# PCB.net
KiCad netlist of a schematic drawn in EAGLE
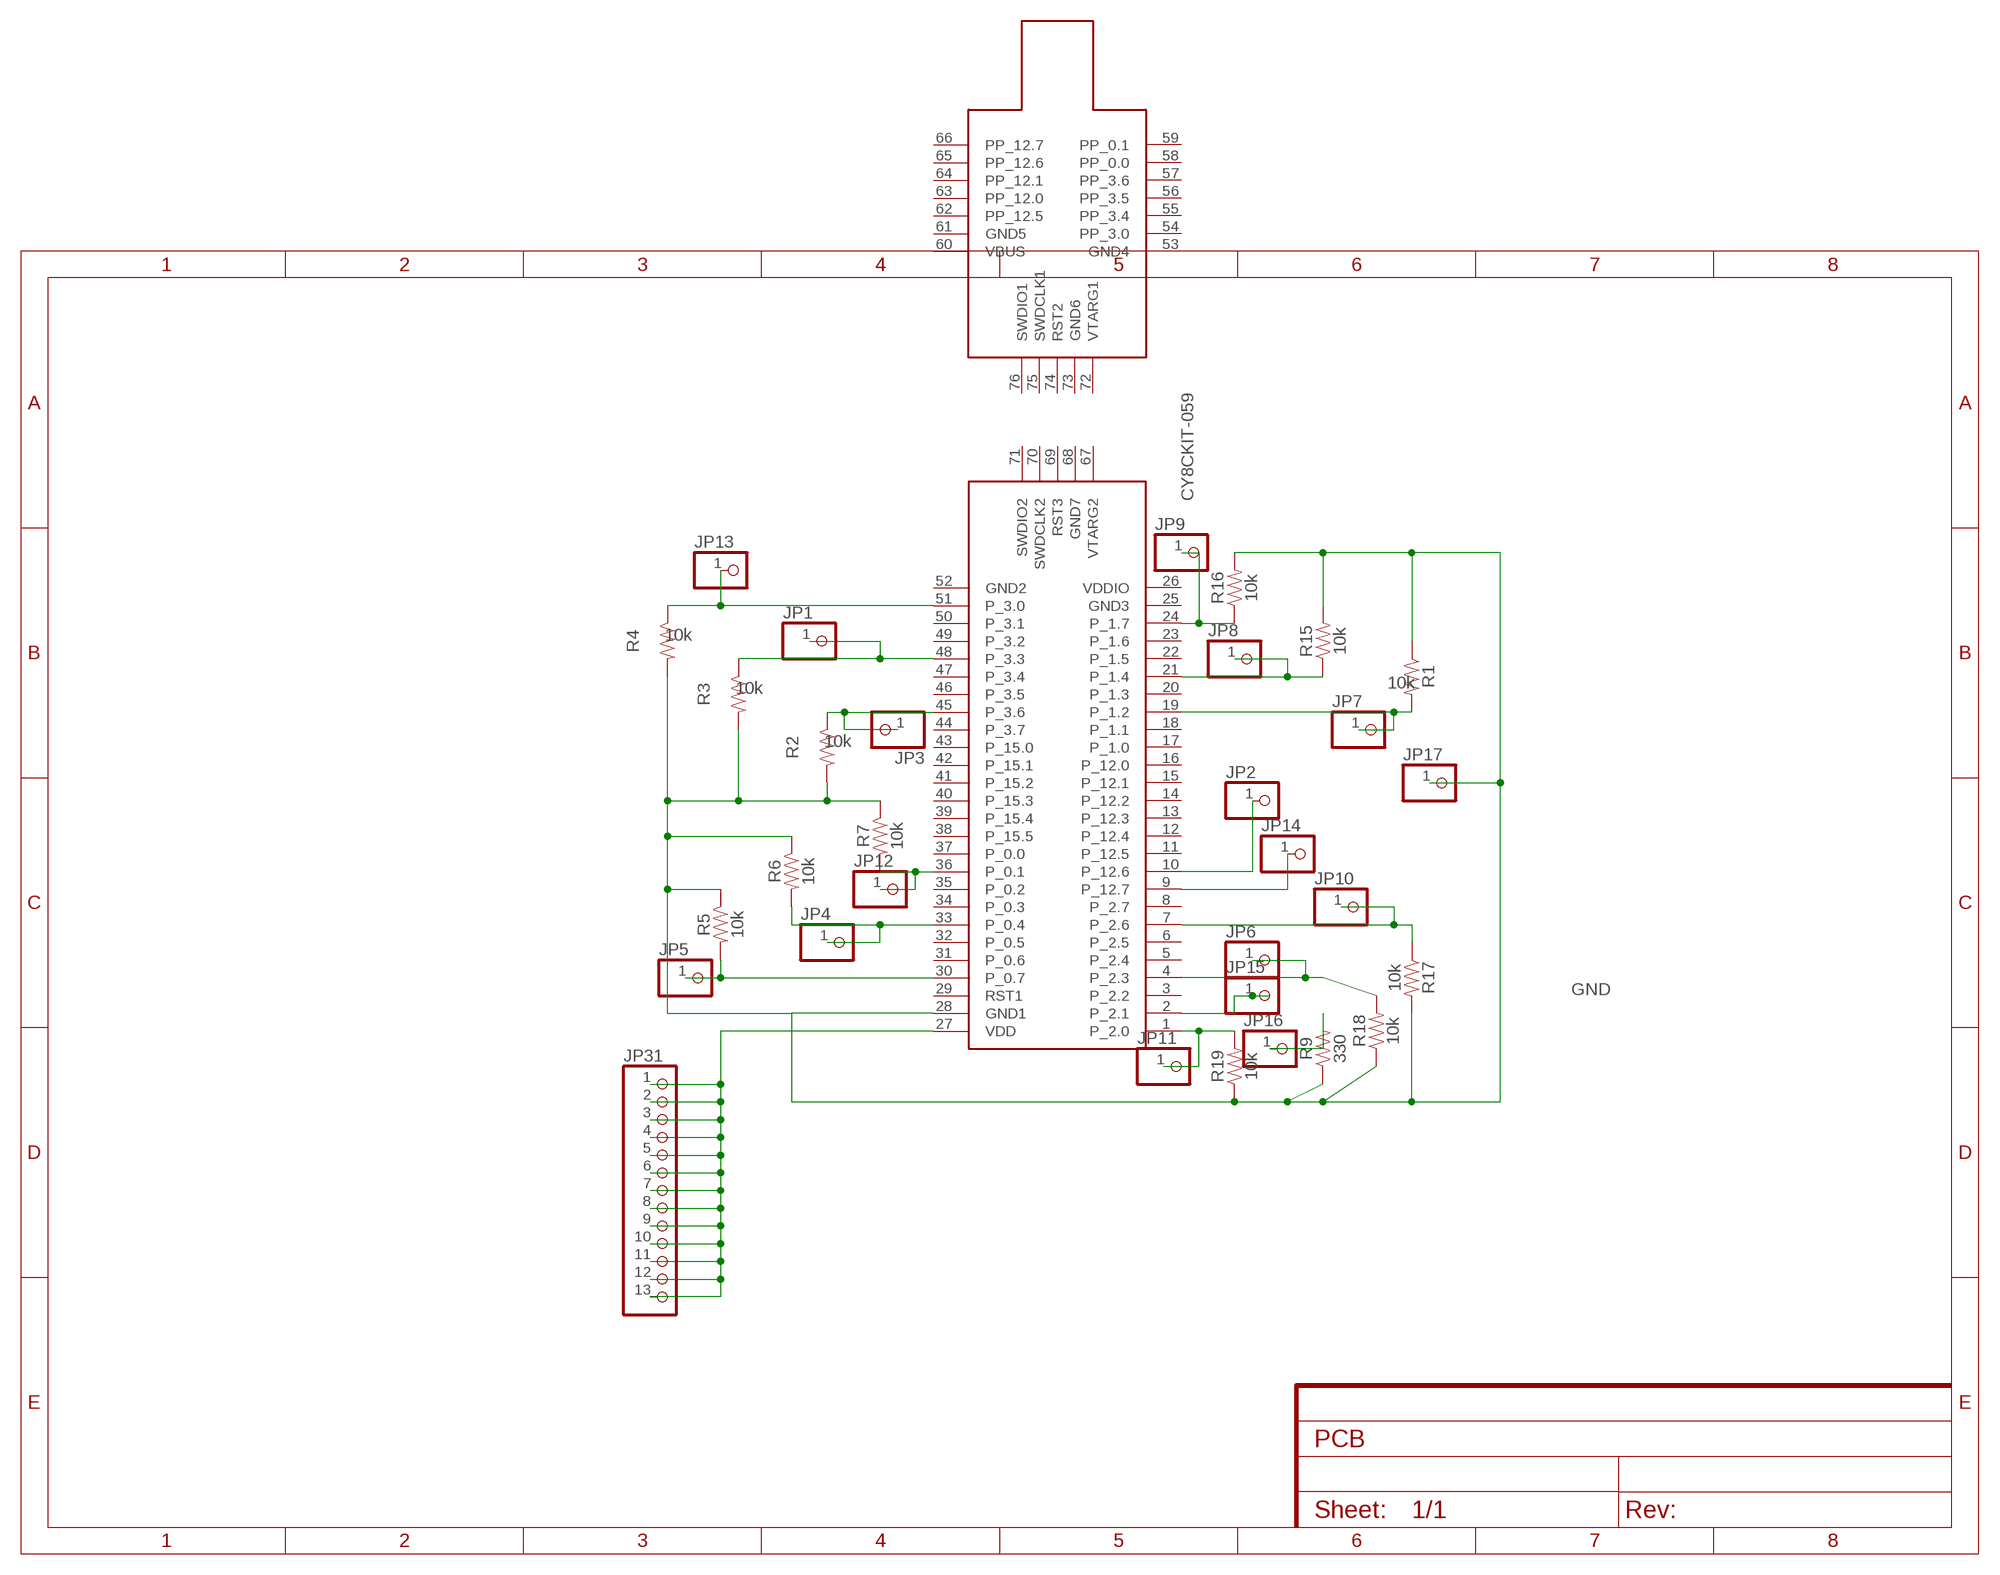
[diagram p0: schematic, sheet 1]

(export (version "E")
  (design (tool "Eeschema 10.0.6"))
  (components
    (comp (ref "JP1")
      (value "PINHD-1X1")
      (footprint "eagle-import:1X01")
      (libsource (lib "eagle-import") (part "PINHD-1X1"))
    )
    (comp (ref "JP2")
      (value "PINHD-1X1")
      (footprint "eagle-import:1X01")
      (libsource (lib "eagle-import") (part "PINHD-1X1"))
    )
    (comp (ref "JP3")
      (value "PINHD-1X1")
      (footprint "eagle-import:1X01")
      (libsource (lib "eagle-import") (part "PINHD-1X1"))
    )
    (comp (ref "JP4")
      (value "PINHD-1X1")
      (footprint "eagle-import:1X01")
      (libsource (lib "eagle-import") (part "PINHD-1X1"))
    )
    (comp (ref "JP5")
      (value "PINHD-1X1")
      (footprint "eagle-import:1X01")
      (libsource (lib "eagle-import") (part "PINHD-1X1"))
    )
    (comp (ref "JP6")
      (value "PINHD-1X1")
      (footprint "eagle-import:1X01")
      (libsource (lib "eagle-import") (part "PINHD-1X1"))
    )
    (comp (ref "JP7")
      (value "PINHD-1X1")
      (footprint "eagle-import:1X01")
      (libsource (lib "eagle-import") (part "PINHD-1X1"))
    )
    (comp (ref "JP8")
      (value "PINHD-1X1")
      (footprint "eagle-import:1X01")
      (libsource (lib "eagle-import") (part "PINHD-1X1"))
    )
    (comp (ref "JP9")
      (value "PINHD-1X1")
      (footprint "eagle-import:1X01")
      (libsource (lib "eagle-import") (part "PINHD-1X1"))
    )
    (comp (ref "JP10")
      (value "PINHD-1X1")
      (footprint "eagle-import:1X01")
      (libsource (lib "eagle-import") (part "PINHD-1X1"))
    )
    (comp (ref "JP11")
      (value "PINHD-1X1")
      (footprint "eagle-import:1X01")
      (libsource (lib "eagle-import") (part "PINHD-1X1"))
    )
    (comp (ref "JP12")
      (value "PINHD-1X1")
      (footprint "eagle-import:1X01")
      (libsource (lib "eagle-import") (part "PINHD-1X1"))
    )
    (comp (ref "JP13")
      (value "PINHD-1X1")
      (footprint "eagle-import:1X01")
      (libsource (lib "eagle-import") (part "PINHD-1X1"))
    )
    (comp (ref "JP14")
      (value "PINHD-1X1")
      (footprint "eagle-import:1X01")
      (libsource (lib "eagle-import") (part "PINHD-1X1"))
    )
    (comp (ref "JP15")
      (value "PINHD-1X1")
      (footprint "eagle-import:1X01")
      (libsource (lib "eagle-import") (part "PINHD-1X1"))
    )
    (comp (ref "JP16")
      (value "PINHD-1X1")
      (footprint "eagle-import:1X01")
      (libsource (lib "eagle-import") (part "PINHD-1X1"))
    )
    (comp (ref "JP17")
      (value "PINHD-1X1")
      (footprint "eagle-import:1X01")
      (libsource (lib "eagle-import") (part "PINHD-1X1"))
    )
    (comp (ref "JP31")
      (value "PINHD-1X13")
      (footprint "eagle-import:1X13")
      (libsource (lib "eagle-import") (part "PINHD-1X13"))
    )
    (comp (ref "R1")
      (value "10k")
      (footprint "eagle-import:AXIAL-0.3")
      (libsource (lib "eagle-import") (part "10KOHM-HORIZ-1/4W-1%"))
    )
    (comp (ref "R2")
      (value "10k")
      (footprint "eagle-import:AXIAL-0.3")
      (libsource (lib "eagle-import") (part "10KOHM-HORIZ-1/4W-1%"))
    )
    (comp (ref "R3")
      (value "10k")
      (footprint "eagle-import:AXIAL-0.3")
      (libsource (lib "eagle-import") (part "10KOHM-HORIZ-1/4W-1%"))
    )
    (comp (ref "R4")
      (value "10k")
      (footprint "eagle-import:AXIAL-0.3")
      (libsource (lib "eagle-import") (part "10KOHM-HORIZ-1/4W-1%"))
    )
    (comp (ref "R5")
      (value "10k")
      (footprint "eagle-import:AXIAL-0.3")
      (libsource (lib "eagle-import") (part "10KOHM-HORIZ-1/4W-1%"))
    )
    (comp (ref "R6")
      (value "10k")
      (footprint "eagle-import:AXIAL-0.3")
      (libsource (lib "eagle-import") (part "10KOHM-HORIZ-1/4W-1%"))
    )
    (comp (ref "R7")
      (value "10k")
      (footprint "eagle-import:AXIAL-0.3")
      (libsource (lib "eagle-import") (part "10KOHM-HORIZ-1/4W-1%"))
    )
    (comp (ref "R9")
      (value "330")
      (footprint "eagle-import:AXIAL-0.3")
      (libsource (lib "eagle-import") (part "330OHM-HORIZ-1/10W-5%"))
    )
    (comp (ref "R15")
      (value "10k")
      (footprint "eagle-import:AXIAL-0.3")
      (libsource (lib "eagle-import") (part "10KOHM-HORIZ-1/4W-1%"))
    )
    (comp (ref "R16")
      (value "10k")
      (footprint "eagle-import:AXIAL-0.3")
      (libsource (lib "eagle-import") (part "10KOHM-HORIZ-1/4W-1%"))
    )
    (comp (ref "R17")
      (value "10k")
      (footprint "eagle-import:AXIAL-0.3")
      (libsource (lib "eagle-import") (part "10KOHM-HORIZ-1/4W-1%"))
    )
    (comp (ref "R18")
      (value "10k")
      (footprint "eagle-import:AXIAL-0.3")
      (libsource (lib "eagle-import") (part "10KOHM-HORIZ-1/4W-1%"))
    )
    (comp (ref "R19")
      (value "10k")
      (footprint "eagle-import:AXIAL-0.3")
      (libsource (lib "eagle-import") (part "10KOHM-HORIZ-1/4W-1%"))
    )
    (comp (ref "U$1")
      (value "CY8CKIT-059")
      (footprint "eagle-import:CY8CKIT-059")
      (libsource (lib "eagle-import") (part "CY8CKIT-059"))
    )
  )
  (nets
    (net (code "1") (name "/GND") (class "Default")
      (node (ref "JP17") (pin "1") (pinfunction "1_1") (pintype "passive"))
      (node (ref "R1") (pin "P$1") (pinfunction "1_P$1") (pintype "passive"))
      (node (ref "R15") (pin "P$2") (pinfunction "2_P$2") (pintype "passive"))
      (node (ref "R16") (pin "P$2") (pinfunction "2_P$2") (pintype "passive"))
      (node (ref "R17") (pin "P$2") (pinfunction "2_P$2") (pintype "passive"))
      (node (ref "R18") (pin "P$1") (pinfunction "1_P$1") (pintype "passive"))
      (node (ref "R19") (pin "P$1") (pinfunction "1_P$1") (pintype "passive"))
      (node (ref "R2") (pin "P$2") (pinfunction "2_P$2") (pintype "passive"))
      (node (ref "R3") (pin "P$2") (pinfunction "2_P$2") (pintype "passive"))
      (node (ref "R4") (pin "P$2") (pinfunction "2_P$2") (pintype "passive"))
      (node (ref "R5") (pin "P$1") (pinfunction "1_P$1") (pintype "passive"))
      (node (ref "R6") (pin "P$1") (pinfunction "1_P$1") (pintype "passive"))
      (node (ref "R7") (pin "P$1") (pinfunction "1_P$1") (pintype "passive"))
      (node (ref "R9") (pin "P$1") (pinfunction "1_P$1") (pintype "passive"))
      (node (ref "U$1") (pin "28") (pinfunction "GND1_28") (pintype "bidirectional"))
    )
    (net (code "2") (name "Net-(R1-2)") (class "Default")
      (node (ref "JP7") (pin "1") (pinfunction "1_1") (pintype "passive"))
      (node (ref "R1") (pin "P$2") (pinfunction "2_P$2") (pintype "passive"))
      (node (ref "U$1") (pin "19") (pinfunction "P_1.2_19") (pintype "bidirectional"))
    )
    (net (code "3") (name "Net-(R2-1)") (class "Default")
      (node (ref "JP3") (pin "1") (pinfunction "1_1") (pintype "passive"))
      (node (ref "R2") (pin "P$1") (pinfunction "1_P$1") (pintype "passive"))
      (node (ref "U$1") (pin "45") (pinfunction "P_3.6_45") (pintype "bidirectional"))
    )
    (net (code "4") (name "Net-(R3-1)") (class "Default")
      (node (ref "JP1") (pin "1") (pinfunction "1_1") (pintype "passive"))
      (node (ref "R3") (pin "P$1") (pinfunction "1_P$1") (pintype "passive"))
      (node (ref "U$1") (pin "48") (pinfunction "P_3.3_48") (pintype "bidirectional"))
    )
    (net (code "5") (name "Net-(R4-1)") (class "Default")
      (node (ref "JP13") (pin "1") (pinfunction "1_1") (pintype "passive"))
      (node (ref "R4") (pin "P$1") (pinfunction "1_P$1") (pintype "passive"))
      (node (ref "U$1") (pin "51") (pinfunction "P_3.0_51") (pintype "bidirectional"))
    )
    (net (code "6") (name "Net-(R5-2)") (class "Default")
      (node (ref "JP5") (pin "1") (pinfunction "1_1") (pintype "passive"))
      (node (ref "R5") (pin "P$2") (pinfunction "2_P$2") (pintype "passive"))
      (node (ref "U$1") (pin "30") (pinfunction "P_0.7_30") (pintype "bidirectional"))
    )
    (net (code "7") (name "Net-(R6-2)") (class "Default")
      (node (ref "JP4") (pin "1") (pinfunction "1_1") (pintype "passive"))
      (node (ref "R6") (pin "P$2") (pinfunction "2_P$2") (pintype "passive"))
      (node (ref "U$1") (pin "33") (pinfunction "P_0.4_33") (pintype "bidirectional"))
    )
    (net (code "8") (name "Net-(R7-2)") (class "Default")
      (node (ref "JP12") (pin "1") (pinfunction "1_1") (pintype "passive"))
      (node (ref "R7") (pin "P$2") (pinfunction "2_P$2") (pintype "passive"))
      (node (ref "U$1") (pin "36") (pinfunction "P_0.1_36") (pintype "bidirectional"))
    )
    (net (code "9") (name "Net-(R9-2)") (class "Default")
      (node (ref "JP16") (pin "1") (pinfunction "1_1") (pintype "passive"))
      (node (ref "R9") (pin "P$2") (pinfunction "2_P$2") (pintype "passive"))
    )
    (net (code "10") (name "Net-(R15-1)") (class "Default")
      (node (ref "JP8") (pin "1") (pinfunction "1_1") (pintype "passive"))
      (node (ref "R15") (pin "P$1") (pinfunction "1_P$1") (pintype "passive"))
      (node (ref "U$1") (pin "21") (pinfunction "P_1.4_21") (pintype "bidirectional"))
    )
    (net (code "11") (name "Net-(R16-1)") (class "Default")
      (node (ref "JP9") (pin "1") (pinfunction "1_1") (pintype "passive"))
      (node (ref "R16") (pin "P$1") (pinfunction "1_P$1") (pintype "passive"))
      (node (ref "U$1") (pin "24") (pinfunction "P_1.7_24") (pintype "bidirectional"))
    )
    (net (code "12") (name "Net-(R17-1)") (class "Default")
      (node (ref "JP10") (pin "1") (pinfunction "1_1") (pintype "passive"))
      (node (ref "R17") (pin "P$1") (pinfunction "1_P$1") (pintype "passive"))
      (node (ref "U$1") (pin "7") (pinfunction "P_2.6_7") (pintype "bidirectional"))
    )
    (net (code "13") (name "Net-(R18-2)") (class "Default")
      (node (ref "JP6") (pin "1") (pinfunction "1_1") (pintype "passive"))
      (node (ref "R18") (pin "P$2") (pinfunction "2_P$2") (pintype "passive"))
      (node (ref "U$1") (pin "4") (pinfunction "P_2.3_4") (pintype "bidirectional"))
    )
    (net (code "14") (name "Net-(R19-2)") (class "Default")
      (node (ref "JP11") (pin "1") (pinfunction "1_1") (pintype "passive"))
      (node (ref "R19") (pin "P$2") (pinfunction "2_P$2") (pintype "passive"))
      (node (ref "U$1") (pin "1") (pinfunction "P_2.0_1") (pintype "bidirectional"))
    )
    (net (code "15") (name "Net-(U$1-P_2.1)") (class "Default")
      (node (ref "JP15") (pin "1") (pinfunction "1_1") (pintype "passive"))
      (node (ref "U$1") (pin "2") (pinfunction "P_2.1_2") (pintype "bidirectional"))
    )
    (net (code "16") (name "Net-(U$1-P_12.6)") (class "Default")
      (node (ref "JP2") (pin "1") (pinfunction "1_1") (pintype "passive"))
      (node (ref "U$1") (pin "10") (pinfunction "P_12.6_10") (pintype "bidirectional"))
    )
    (net (code "17") (name "Net-(U$1-P_12.7)") (class "Default")
      (node (ref "JP14") (pin "1") (pinfunction "1_1") (pintype "passive"))
      (node (ref "U$1") (pin "9") (pinfunction "P_12.7_9") (pintype "bidirectional"))
    )
    (net (code "18") (name "Net-(U$1-VDD)") (class "Default")
      (node (ref "JP31") (pin "1") (pinfunction "1_1") (pintype "passive"))
      (node (ref "JP31") (pin "10") (pinfunction "10_10") (pintype "passive"))
      (node (ref "JP31") (pin "11") (pinfunction "11_11") (pintype "passive"))
      (node (ref "JP31") (pin "12") (pinfunction "12_12") (pintype "passive"))
      (node (ref "JP31") (pin "13") (pinfunction "13_13") (pintype "passive"))
      (node (ref "JP31") (pin "2") (pinfunction "2_2") (pintype "passive"))
      (node (ref "JP31") (pin "3") (pinfunction "3_3") (pintype "passive"))
      (node (ref "JP31") (pin "4") (pinfunction "4_4") (pintype "passive"))
      (node (ref "JP31") (pin "5") (pinfunction "5_5") (pintype "passive"))
      (node (ref "JP31") (pin "6") (pinfunction "6_6") (pintype "passive"))
      (node (ref "JP31") (pin "7") (pinfunction "7_7") (pintype "passive"))
      (node (ref "JP31") (pin "8") (pinfunction "8_8") (pintype "passive"))
      (node (ref "JP31") (pin "9") (pinfunction "9_9") (pintype "passive"))
      (node (ref "U$1") (pin "27") (pinfunction "VDD_27") (pintype "bidirectional"))
    )
    (net (code "19") (name "unconnected-(U$1-GND2-Pad52)") (class "Default")
      (node (ref "U$1") (pin "52") (pinfunction "GND2_52") (pintype "bidirectional"))
    )
    (net (code "20") (name "unconnected-(U$1-GND3-Pad25)") (class "Default")
      (node (ref "U$1") (pin "25") (pinfunction "GND3_25") (pintype "bidirectional"))
    )
    (net (code "21") (name "unconnected-(U$1-GND4-Pad53)") (class "Default")
      (node (ref "U$1") (pin "53") (pinfunction "GND4_53") (pintype "bidirectional"))
    )
    (net (code "22") (name "unconnected-(U$1-GND5-Pad61)") (class "Default")
      (node (ref "U$1") (pin "61") (pinfunction "GND5_61") (pintype "bidirectional"))
    )
    (net (code "23") (name "unconnected-(U$1-GND6-Pad73)") (class "Default")
      (node (ref "U$1") (pin "73") (pinfunction "GND6_73") (pintype "bidirectional"))
    )
    (net (code "24") (name "unconnected-(U$1-GND7-Pad68)") (class "Default")
      (node (ref "U$1") (pin "68") (pinfunction "GND7_68") (pintype "bidirectional"))
    )
    (net (code "25") (name "unconnected-(U$1-PP_0.0-Pad58)") (class "Default")
      (node (ref "U$1") (pin "58") (pinfunction "PP_0.0_58") (pintype "bidirectional"))
    )
    (net (code "26") (name "unconnected-(U$1-PP_0.1-Pad59)") (class "Default")
      (node (ref "U$1") (pin "59") (pinfunction "PP_0.1_59") (pintype "bidirectional"))
    )
    (net (code "27") (name "unconnected-(U$1-PP_3.0-Pad54)") (class "Default")
      (node (ref "U$1") (pin "54") (pinfunction "PP_3.0_54") (pintype "bidirectional"))
    )
    (net (code "28") (name "unconnected-(U$1-PP_3.4-Pad55)") (class "Default")
      (node (ref "U$1") (pin "55") (pinfunction "PP_3.4_55") (pintype "bidirectional"))
    )
    (net (code "29") (name "unconnected-(U$1-PP_3.5-Pad56)") (class "Default")
      (node (ref "U$1") (pin "56") (pinfunction "PP_3.5_56") (pintype "bidirectional"))
    )
    (net (code "30") (name "unconnected-(U$1-PP_3.6-Pad57)") (class "Default")
      (node (ref "U$1") (pin "57") (pinfunction "PP_3.6_57") (pintype "bidirectional"))
    )
    (net (code "31") (name "unconnected-(U$1-PP_12.0-Pad63)") (class "Default")
      (node (ref "U$1") (pin "63") (pinfunction "PP_12.0_63") (pintype "bidirectional"))
    )
    (net (code "32") (name "unconnected-(U$1-PP_12.1-Pad64)") (class "Default")
      (node (ref "U$1") (pin "64") (pinfunction "PP_12.1_64") (pintype "bidirectional"))
    )
    (net (code "33") (name "unconnected-(U$1-PP_12.5-Pad62)") (class "Default")
      (node (ref "U$1") (pin "62") (pinfunction "PP_12.5_62") (pintype "bidirectional"))
    )
    (net (code "34") (name "unconnected-(U$1-PP_12.6-Pad65)") (class "Default")
      (node (ref "U$1") (pin "65") (pinfunction "PP_12.6_65") (pintype "bidirectional"))
    )
    (net (code "35") (name "unconnected-(U$1-PP_12.7-Pad66)") (class "Default")
      (node (ref "U$1") (pin "66") (pinfunction "PP_12.7_66") (pintype "bidirectional"))
    )
    (net (code "36") (name "unconnected-(U$1-P_0.0-Pad37)") (class "Default")
      (node (ref "U$1") (pin "37") (pinfunction "P_0.0_37") (pintype "bidirectional"))
    )
    (net (code "37") (name "unconnected-(U$1-P_0.2-Pad35)") (class "Default")
      (node (ref "U$1") (pin "35") (pinfunction "P_0.2_35") (pintype "bidirectional"))
    )
    (net (code "38") (name "unconnected-(U$1-P_0.3-Pad34)") (class "Default")
      (node (ref "U$1") (pin "34") (pinfunction "P_0.3_34") (pintype "bidirectional"))
    )
    (net (code "39") (name "unconnected-(U$1-P_0.5-Pad32)") (class "Default")
      (node (ref "U$1") (pin "32") (pinfunction "P_0.5_32") (pintype "bidirectional"))
    )
    (net (code "40") (name "unconnected-(U$1-P_0.6-Pad31)") (class "Default")
      (node (ref "U$1") (pin "31") (pinfunction "P_0.6_31") (pintype "bidirectional"))
    )
    (net (code "41") (name "unconnected-(U$1-P_1.0-Pad17)") (class "Default")
      (node (ref "U$1") (pin "17") (pinfunction "P_1.0_17") (pintype "bidirectional"))
    )
    (net (code "42") (name "unconnected-(U$1-P_1.1-Pad18)") (class "Default")
      (node (ref "U$1") (pin "18") (pinfunction "P_1.1_18") (pintype "bidirectional"))
    )
    (net (code "43") (name "unconnected-(U$1-P_1.3-Pad20)") (class "Default")
      (node (ref "U$1") (pin "20") (pinfunction "P_1.3_20") (pintype "bidirectional"))
    )
    (net (code "44") (name "unconnected-(U$1-P_1.5-Pad22)") (class "Default")
      (node (ref "U$1") (pin "22") (pinfunction "P_1.5_22") (pintype "bidirectional"))
    )
    (net (code "45") (name "unconnected-(U$1-P_1.6-Pad23)") (class "Default")
      (node (ref "U$1") (pin "23") (pinfunction "P_1.6_23") (pintype "bidirectional"))
    )
    (net (code "46") (name "unconnected-(U$1-P_2.2-Pad3)") (class "Default")
      (node (ref "U$1") (pin "3") (pinfunction "P_2.2_3") (pintype "bidirectional"))
    )
    (net (code "47") (name "unconnected-(U$1-P_2.4-Pad5)") (class "Default")
      (node (ref "U$1") (pin "5") (pinfunction "P_2.4_5") (pintype "bidirectional"))
    )
    (net (code "48") (name "unconnected-(U$1-P_2.5-Pad6)") (class "Default")
      (node (ref "U$1") (pin "6") (pinfunction "P_2.5_6") (pintype "bidirectional"))
    )
    (net (code "49") (name "unconnected-(U$1-P_2.7-Pad8)") (class "Default")
      (node (ref "U$1") (pin "8") (pinfunction "P_2.7_8") (pintype "bidirectional"))
    )
    (net (code "50") (name "unconnected-(U$1-P_3.1-Pad50)") (class "Default")
      (node (ref "U$1") (pin "50") (pinfunction "P_3.1_50") (pintype "bidirectional"))
    )
    (net (code "51") (name "unconnected-(U$1-P_3.2-Pad49)") (class "Default")
      (node (ref "U$1") (pin "49") (pinfunction "P_3.2_49") (pintype "bidirectional"))
    )
    (net (code "52") (name "unconnected-(U$1-P_3.4-Pad47)") (class "Default")
      (node (ref "U$1") (pin "47") (pinfunction "P_3.4_47") (pintype "bidirectional"))
    )
    (net (code "53") (name "unconnected-(U$1-P_3.5-Pad46)") (class "Default")
      (node (ref "U$1") (pin "46") (pinfunction "P_3.5_46") (pintype "bidirectional"))
    )
    (net (code "54") (name "unconnected-(U$1-P_3.7-Pad44)") (class "Default")
      (node (ref "U$1") (pin "44") (pinfunction "P_3.7_44") (pintype "bidirectional"))
    )
    (net (code "55") (name "unconnected-(U$1-P_12.0-Pad16)") (class "Default")
      (node (ref "U$1") (pin "16") (pinfunction "P_12.0_16") (pintype "bidirectional"))
    )
    (net (code "56") (name "unconnected-(U$1-P_12.1-Pad15)") (class "Default")
      (node (ref "U$1") (pin "15") (pinfunction "P_12.1_15") (pintype "bidirectional"))
    )
    (net (code "57") (name "unconnected-(U$1-P_12.2-Pad14)") (class "Default")
      (node (ref "U$1") (pin "14") (pinfunction "P_12.2_14") (pintype "bidirectional"))
    )
    (net (code "58") (name "unconnected-(U$1-P_12.3-Pad13)") (class "Default")
      (node (ref "U$1") (pin "13") (pinfunction "P_12.3_13") (pintype "bidirectional"))
    )
    (net (code "59") (name "unconnected-(U$1-P_12.4-Pad12)") (class "Default")
      (node (ref "U$1") (pin "12") (pinfunction "P_12.4_12") (pintype "bidirectional"))
    )
    (net (code "60") (name "unconnected-(U$1-P_12.5-Pad11)") (class "Default")
      (node (ref "U$1") (pin "11") (pinfunction "P_12.5_11") (pintype "bidirectional"))
    )
    (net (code "61") (name "unconnected-(U$1-P_15.0-Pad43)") (class "Default")
      (node (ref "U$1") (pin "43") (pinfunction "P_15.0_43") (pintype "bidirectional"))
    )
    (net (code "62") (name "unconnected-(U$1-P_15.1-Pad42)") (class "Default")
      (node (ref "U$1") (pin "42") (pinfunction "P_15.1_42") (pintype "bidirectional"))
    )
    (net (code "63") (name "unconnected-(U$1-P_15.2-Pad41)") (class "Default")
      (node (ref "U$1") (pin "41") (pinfunction "P_15.2_41") (pintype "bidirectional"))
    )
    (net (code "64") (name "unconnected-(U$1-P_15.3-Pad40)") (class "Default")
      (node (ref "U$1") (pin "40") (pinfunction "P_15.3_40") (pintype "bidirectional"))
    )
    (net (code "65") (name "unconnected-(U$1-P_15.4-Pad39)") (class "Default")
      (node (ref "U$1") (pin "39") (pinfunction "P_15.4_39") (pintype "bidirectional"))
    )
    (net (code "66") (name "unconnected-(U$1-P_15.5-Pad38)") (class "Default")
      (node (ref "U$1") (pin "38") (pinfunction "P_15.5_38") (pintype "bidirectional"))
    )
    (net (code "67") (name "unconnected-(U$1-RST1-Pad29)") (class "Default")
      (node (ref "U$1") (pin "29") (pinfunction "RST1_29") (pintype "bidirectional"))
    )
    (net (code "68") (name "unconnected-(U$1-RST2-Pad74)") (class "Default")
      (node (ref "U$1") (pin "74") (pinfunction "RST2_74") (pintype "bidirectional"))
    )
    (net (code "69") (name "unconnected-(U$1-RST3-Pad69)") (class "Default")
      (node (ref "U$1") (pin "69") (pinfunction "RST3_69") (pintype "bidirectional"))
    )
    (net (code "70") (name "unconnected-(U$1-SWDCLK1-Pad75)") (class "Default")
      (node (ref "U$1") (pin "75") (pinfunction "SWDCLK1_75") (pintype "bidirectional"))
    )
    (net (code "71") (name "unconnected-(U$1-SWDCLK2-Pad70)") (class "Default")
      (node (ref "U$1") (pin "70") (pinfunction "SWDCLK2_70") (pintype "bidirectional"))
    )
    (net (code "72") (name "unconnected-(U$1-SWDIO1-Pad76)") (class "Default")
      (node (ref "U$1") (pin "76") (pinfunction "SWDIO1_76") (pintype "bidirectional"))
    )
    (net (code "73") (name "unconnected-(U$1-SWDIO2-Pad71)") (class "Default")
      (node (ref "U$1") (pin "71") (pinfunction "SWDIO2_71") (pintype "bidirectional"))
    )
    (net (code "74") (name "unconnected-(U$1-VBUS-Pad60)") (class "Default")
      (node (ref "U$1") (pin "60") (pinfunction "VBUS_60") (pintype "bidirectional"))
    )
    (net (code "75") (name "unconnected-(U$1-VDDIO-Pad26)") (class "Default")
      (node (ref "U$1") (pin "26") (pinfunction "VDDIO_26") (pintype "bidirectional"))
    )
    (net (code "76") (name "unconnected-(U$1-VTARG1-Pad72)") (class "Default")
      (node (ref "U$1") (pin "72") (pinfunction "VTARG1_72") (pintype "bidirectional"))
    )
    (net (code "77") (name "unconnected-(U$1-VTARG2-Pad67)") (class "Default")
      (node (ref "U$1") (pin "67") (pinfunction "VTARG2_67") (pintype "bidirectional"))
    )
  )
)
